# schematic_v2.net
KiCad netlist of a schematic drawn in EAGLE
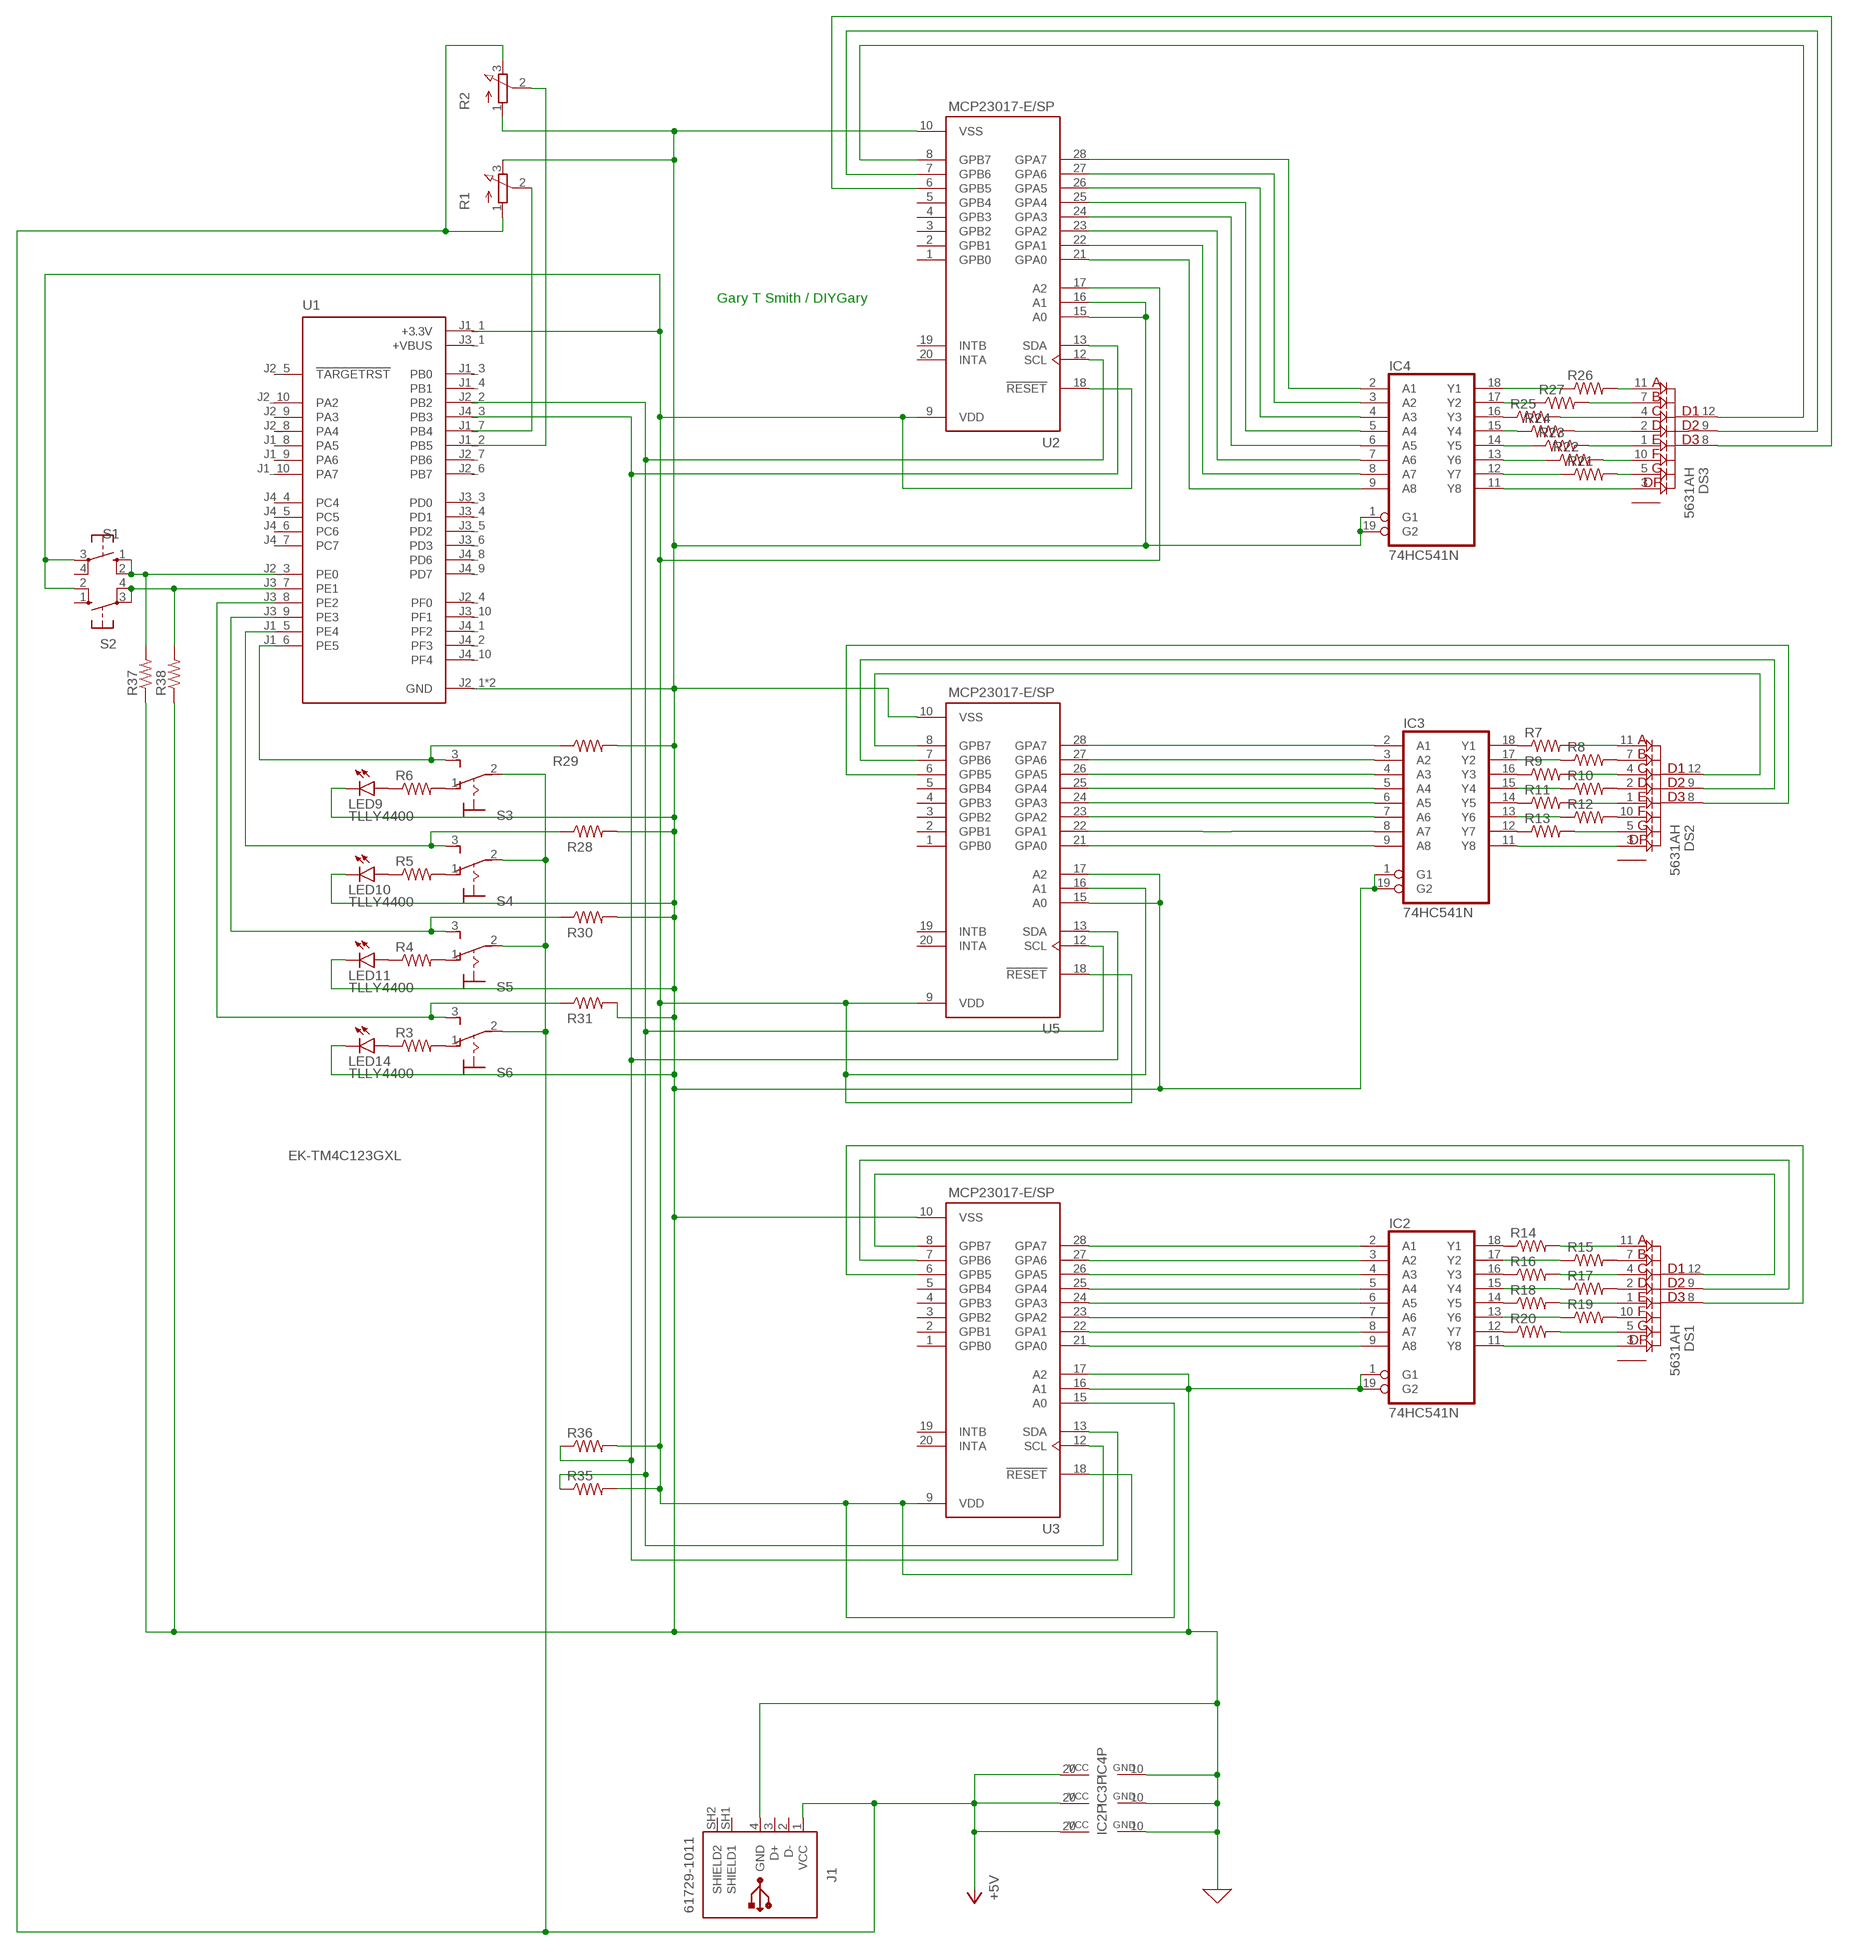
[diagram p0: schematic, sheet 1]

(export (version "E")
  (design (tool "Eeschema 10.0.6"))
  (components
    (comp (ref "DS1")
      (value "5631AH")
      (footprint "eagle-import:DIPS1524W50P254L3760H835Q12N")
      (fields
        (field (name "MANUFACTURER_PART_NUMBER") "BC56-12SRWA")
        (field (name "MOUSER_PART_NUMBER") "604-BC56-12SRWA")
      )
      (libsource (lib "eagle-import") (part "5631AH"))
    )
    (comp (ref "DS2")
      (value "5631AH")
      (footprint "eagle-import:DIPS1524W50P254L3760H835Q12N")
      (fields
        (field (name "MANUFACTURER_PART_NUMBER") "BC56-12SRWA")
        (field (name "MOUSER_PART_NUMBER") "604-BC56-12SRWA")
      )
      (libsource (lib "eagle-import") (part "5631AH"))
    )
    (comp (ref "DS3")
      (value "5631AH")
      (footprint "eagle-import:DIPS1524W50P254L3760H835Q12N")
      (fields
        (field (name "MANUFACTURER_PART_NUMBER") "BC56-12SRWA")
        (field (name "MOUSER_PART_NUMBER") "604-BC56-12SRWA")
      )
      (libsource (lib "eagle-import") (part "5631AH"))
    )
    (comp (ref "IC2")
      (value "74HC541N")
      (footprint "eagle-import:DIL20")
      (libsource (lib "eagle-import") (part "74541NHC"))
    )
    (comp (ref "IC3")
      (value "74HC541N")
      (footprint "eagle-import:DIL20")
      (libsource (lib "eagle-import") (part "74541NHC"))
    )
    (comp (ref "IC4")
      (value "74HC541N")
      (footprint "eagle-import:DIL20")
      (libsource (lib "eagle-import") (part "74541NHC"))
    )
    (comp (ref "J1")
      (value "61729-1011")
      (footprint "eagle-import:61729-1011BLF")
      (fields (field (name "MANUFACTURER") "Amphenol ICC (FCI)") (field (name "MPN") "61729-1011BLF"))
      (libsource (lib "eagle-import") (part "61729-1011"))
    )
    (comp (ref "LED9")
      (value "TLLY4400")
      (footprint "eagle-import:LED3MM")
      (fields (field (name "MF") "VISHAY SEMICONDUCTOR"))
      (libsource (lib "eagle-import") (part "TLLY4400"))
    )
    (comp (ref "LED10")
      (value "TLLY4400")
      (footprint "eagle-import:LED3MM")
      (fields (field (name "MF") "VISHAY SEMICONDUCTOR"))
      (libsource (lib "eagle-import") (part "TLLY4400"))
    )
    (comp (ref "LED11")
      (value "TLLY4400")
      (footprint "eagle-import:LED3MM")
      (fields (field (name "MF") "VISHAY SEMICONDUCTOR"))
      (libsource (lib "eagle-import") (part "TLLY4400"))
    )
    (comp (ref "LED14")
      (value "TLLY4400")
      (footprint "eagle-import:LED3MM")
      (fields (field (name "MF") "VISHAY SEMICONDUCTOR"))
      (libsource (lib "eagle-import") (part "TLLY4400"))
    )
    (comp (ref "R1")
      (value "3RP/1610N")
      (footprint "eagle-import:3RP_1610N")
      (libsource (lib "eagle-import") (part "3RP/1610N"))
    )
    (comp (ref "R2")
      (value "3RP/1610N")
      (footprint "eagle-import:3RP_1610N")
      (libsource (lib "eagle-import") (part "3RP/1610N"))
    )
    (comp (ref "R3")
      (value "R-US_0204/7")
      (footprint "eagle-import:0204_7")
      (libsource (lib "eagle-import") (part "R-US_0204/7"))
    )
    (comp (ref "R4")
      (value "R-US_0204/7")
      (footprint "eagle-import:0204_7")
      (libsource (lib "eagle-import") (part "R-US_0204/7"))
    )
    (comp (ref "R5")
      (value "R-US_0204/7")
      (footprint "eagle-import:0204_7")
      (libsource (lib "eagle-import") (part "R-US_0204/7"))
    )
    (comp (ref "R6")
      (value "R-US_0204/7")
      (footprint "eagle-import:0204_7")
      (libsource (lib "eagle-import") (part "R-US_0204/7"))
    )
    (comp (ref "R7")
      (value "R-US_0204/7")
      (footprint "eagle-import:0204_7")
      (libsource (lib "eagle-import") (part "R-US_0204/7"))
    )
    (comp (ref "R8")
      (value "R-US_0204/7")
      (footprint "eagle-import:0204_7")
      (libsource (lib "eagle-import") (part "R-US_0204/7"))
    )
    (comp (ref "R9")
      (value "R-US_0204/7")
      (footprint "eagle-import:0204_7")
      (libsource (lib "eagle-import") (part "R-US_0204/7"))
    )
    (comp (ref "R10")
      (value "R-US_0204/7")
      (footprint "eagle-import:0204_7")
      (libsource (lib "eagle-import") (part "R-US_0204/7"))
    )
    (comp (ref "R11")
      (value "R-US_0204/7")
      (footprint "eagle-import:0204_7")
      (libsource (lib "eagle-import") (part "R-US_0204/7"))
    )
    (comp (ref "R12")
      (value "R-US_0204/7")
      (footprint "eagle-import:0204_7")
      (libsource (lib "eagle-import") (part "R-US_0204/7"))
    )
    (comp (ref "R13")
      (value "R-US_0204/7")
      (footprint "eagle-import:0204_7")
      (libsource (lib "eagle-import") (part "R-US_0204/7"))
    )
    (comp (ref "R14")
      (value "R-US_0204/7")
      (footprint "eagle-import:0204_7")
      (libsource (lib "eagle-import") (part "R-US_0204/7"))
    )
    (comp (ref "R15")
      (value "R-US_0204/7")
      (footprint "eagle-import:0204_7")
      (libsource (lib "eagle-import") (part "R-US_0204/7"))
    )
    (comp (ref "R16")
      (value "R-US_0204/7")
      (footprint "eagle-import:0204_7")
      (libsource (lib "eagle-import") (part "R-US_0204/7"))
    )
    (comp (ref "R17")
      (value "R-US_0204/7")
      (footprint "eagle-import:0204_7")
      (libsource (lib "eagle-import") (part "R-US_0204/7"))
    )
    (comp (ref "R18")
      (value "R-US_0204/7")
      (footprint "eagle-import:0204_7")
      (libsource (lib "eagle-import") (part "R-US_0204/7"))
    )
    (comp (ref "R19")
      (value "R-US_0204/7")
      (footprint "eagle-import:0204_7")
      (libsource (lib "eagle-import") (part "R-US_0204/7"))
    )
    (comp (ref "R20")
      (value "R-US_0204/7")
      (footprint "eagle-import:0204_7")
      (libsource (lib "eagle-import") (part "R-US_0204/7"))
    )
    (comp (ref "R21")
      (value "R-US_0204/7")
      (footprint "eagle-import:0204_7")
      (libsource (lib "eagle-import") (part "R-US_0204/7"))
    )
    (comp (ref "R22")
      (value "R-US_0204/7")
      (footprint "eagle-import:0204_7")
      (libsource (lib "eagle-import") (part "R-US_0204/7"))
    )
    (comp (ref "R23")
      (value "R-US_0204/7")
      (footprint "eagle-import:0204_7")
      (libsource (lib "eagle-import") (part "R-US_0204/7"))
    )
    (comp (ref "R24")
      (value "R-US_0204/7")
      (footprint "eagle-import:0204_7")
      (libsource (lib "eagle-import") (part "R-US_0204/7"))
    )
    (comp (ref "R25")
      (value "R-US_0204/7")
      (footprint "eagle-import:0204_7")
      (libsource (lib "eagle-import") (part "R-US_0204/7"))
    )
    (comp (ref "R26")
      (value "R-US_0204/7")
      (footprint "eagle-import:0204_7")
      (libsource (lib "eagle-import") (part "R-US_0204/7"))
    )
    (comp (ref "R27")
      (value "R-US_0204/7")
      (footprint "eagle-import:0204_7")
      (libsource (lib "eagle-import") (part "R-US_0204/7"))
    )
    (comp (ref "R28")
      (value "R-US_0204/7")
      (footprint "eagle-import:0204_7")
      (libsource (lib "eagle-import") (part "R-US_0204/7"))
    )
    (comp (ref "R29")
      (value "R-US_0204/7")
      (footprint "eagle-import:0204_7")
      (libsource (lib "eagle-import") (part "R-US_0204/7"))
    )
    (comp (ref "R30")
      (value "R-US_0204/7")
      (footprint "eagle-import:0204_7")
      (libsource (lib "eagle-import") (part "R-US_0204/7"))
    )
    (comp (ref "R31")
      (value "R-US_0204/7")
      (footprint "eagle-import:0204_7")
      (libsource (lib "eagle-import") (part "R-US_0204/7"))
    )
    (comp (ref "R35")
      (value "R-US_0204/7")
      (footprint "eagle-import:0204_7")
      (libsource (lib "eagle-import") (part "R-US_0204/7"))
    )
    (comp (ref "R36")
      (value "R-US_0204/7")
      (footprint "eagle-import:0204_7")
      (libsource (lib "eagle-import") (part "R-US_0204/7"))
    )
    (comp (ref "R37")
      (value "R-US_0204/7")
      (footprint "eagle-import:0204_7")
      (libsource (lib "eagle-import") (part "R-US_0204/7"))
    )
    (comp (ref "R38")
      (value "R-US_0204/7")
      (footprint "eagle-import:0204_7")
      (libsource (lib "eagle-import") (part "R-US_0204/7"))
    )
    (comp (ref "S1")
      (value "10-XX")
      (footprint "eagle-import:B3F-10XX")
      (fields (field (name "MPN") "B3F-1000"))
      (libsource (lib "eagle-import") (part "10-XX"))
    )
    (comp (ref "S2")
      (value "10-XX")
      (footprint "eagle-import:B3F-10XX")
      (fields (field (name "MPN") "B3F-1000"))
      (libsource (lib "eagle-import") (part "10-XX"))
    )
    (comp (ref "S3")
      (value "320-916")
      (footprint "eagle-import:320-916")
      (libsource (lib "eagle-import") (part "320-916"))
    )
    (comp (ref "S4")
      (value "320-916")
      (footprint "eagle-import:320-916")
      (libsource (lib "eagle-import") (part "320-916"))
    )
    (comp (ref "S5")
      (value "320-916")
      (footprint "eagle-import:320-916")
      (libsource (lib "eagle-import") (part "320-916"))
    )
    (comp (ref "S6")
      (value "320-916")
      (footprint "eagle-import:320-916")
      (libsource (lib "eagle-import") (part "320-916"))
    )
    (comp (ref "U1")
      (value "EK-TM4C123GXL")
      (footprint "eagle-import:MODULE_EK-TM4C123GXL")
      (fields (field (name "MF") "Texas Instruments"))
      (libsource (lib "eagle-import") (part "EK-TM4C123GXL"))
    )
    (comp (ref "U2")
      (value "MCP23017-E/SP")
      (footprint "eagle-import:DIP787W45P254L3556H508Q28")
      (fields (field (name "MF") "Microchip Technology"))
      (libsource (lib "eagle-import") (part "MCP23017-E/SP"))
    )
    (comp (ref "U3")
      (value "MCP23017-E/SP")
      (footprint "eagle-import:DIP787W45P254L3556H508Q28")
      (fields (field (name "MF") "Microchip Technology"))
      (libsource (lib "eagle-import") (part "MCP23017-E/SP"))
    )
    (comp (ref "U5")
      (value "MCP23017-E/SP")
      (footprint "eagle-import:DIP787W45P254L3556H508Q28")
      (fields (field (name "MF") "Microchip Technology"))
      (libsource (lib "eagle-import") (part "MCP23017-E/SP"))
    )
  )
  (nets
    (net (code "1") (name "+5V") (class "Default")
      (node (ref "IC2") (pin "20") (pinfunction "VCC_20") (pintype "power_in"))
      (node (ref "IC3") (pin "20") (pinfunction "VCC_20") (pintype "power_in"))
      (node (ref "IC4") (pin "20") (pinfunction "VCC_20") (pintype "power_in"))
      (node (ref "J1") (pin "1") (pinfunction "VCC_1") (pintype "power_in"))
      (node (ref "R1") (pin "1") (pinfunction "A_1") (pintype "passive"))
      (node (ref "R2") (pin "3") (pinfunction "E_3") (pintype "passive"))
      (node (ref "S3") (pin "2") (pinfunction "P_2") (pintype "passive"))
      (node (ref "S4") (pin "2") (pinfunction "P_2") (pintype "passive"))
      (node (ref "S5") (pin "2") (pinfunction "P_2") (pintype "passive"))
      (node (ref "S6") (pin "2") (pinfunction "P_2") (pintype "passive"))
    )
    (net (code "2") (name "/+VBUS") (class "Default")
      (node (ref "U1") (pin "J3_1") (pinfunction "+VBUS_J3_1") (pintype "power_in"))
    )
    (net (code "3") (name "/SHIELD1") (class "Default")
      (node (ref "J1") (pin "SH1") (pinfunction "SHIELD1_SH1") (pintype "power_in"))
    )
    (net (code "4") (name "/SHIELD2") (class "Default")
      (node (ref "J1") (pin "SH2") (pinfunction "SHIELD2_SH2") (pintype "power_in"))
    )
    (net (code "5") (name "GND") (class "Default")
      (node (ref "IC2") (pin "1") (pinfunction "G1_1") (pintype "input"))
      (node (ref "IC2") (pin "10") (pinfunction "GND_10") (pintype "power_in"))
      (node (ref "IC2") (pin "19") (pinfunction "G2_19") (pintype "input"))
      (node (ref "IC3") (pin "1") (pinfunction "G1_1") (pintype "input"))
      (node (ref "IC3") (pin "10") (pinfunction "GND_10") (pintype "power_in"))
      (node (ref "IC3") (pin "19") (pinfunction "G2_19") (pintype "input"))
      (node (ref "IC4") (pin "1") (pinfunction "G1_1") (pintype "input"))
      (node (ref "IC4") (pin "10") (pinfunction "GND_10") (pintype "power_in"))
      (node (ref "IC4") (pin "19") (pinfunction "G2_19") (pintype "input"))
      (node (ref "J1") (pin "4") (pinfunction "GND_4") (pintype "power_in"))
      (node (ref "LED10") (pin "K") (pinfunction "C_K") (pintype "passive"))
      (node (ref "LED11") (pin "K") (pinfunction "C_K") (pintype "passive"))
      (node (ref "LED14") (pin "K") (pinfunction "C_K") (pintype "passive"))
      (node (ref "LED9") (pin "K") (pinfunction "C_K") (pintype "passive"))
      (node (ref "R1") (pin "3") (pinfunction "E_3") (pintype "passive"))
      (node (ref "R2") (pin "1") (pinfunction "A_1") (pintype "passive"))
      (node (ref "R28") (pin "2") (pinfunction "2_2") (pintype "passive"))
      (node (ref "R29") (pin "2") (pinfunction "2_2") (pintype "passive"))
      (node (ref "R30") (pin "2") (pinfunction "2_2") (pintype "passive"))
      (node (ref "R31") (pin "2") (pinfunction "2_2") (pintype "passive"))
      (node (ref "R37") (pin "1") (pinfunction "1_1") (pintype "passive"))
      (node (ref "R38") (pin "1") (pinfunction "1_1") (pintype "passive"))
      (node (ref "U1") (pin "J2_1") (pinfunction "GND_J2_1") (pintype "power_in"))
      (node (ref "U1") (pin "J3_2") (pinfunction "GND_J3_2") (pintype "power_in"))
      (node (ref "U2") (pin "10") (pinfunction "VSS_10") (pintype "power_in"))
      (node (ref "U2") (pin "15") (pinfunction "A0_15") (pintype "input"))
      (node (ref "U2") (pin "16") (pinfunction "A1_16") (pintype "input"))
      (node (ref "U3") (pin "10") (pinfunction "VSS_10") (pintype "power_in"))
      (node (ref "U3") (pin "16") (pinfunction "A1_16") (pintype "input"))
      (node (ref "U3") (pin "17") (pinfunction "A2_17") (pintype "input"))
      (node (ref "U5") (pin "10") (pinfunction "VSS_10") (pintype "power_in"))
      (node (ref "U5") (pin "15") (pinfunction "A0_15") (pintype "input"))
      (node (ref "U5") (pin "17") (pinfunction "A2_17") (pintype "input"))
    )
    (net (code "6") (name "Net-(DS1-A_A)") (class "Default")
      (node (ref "DS1") (pin "11") (pinfunction "A_A_11") (pintype "bidirectional"))
      (node (ref "R14") (pin "2") (pinfunction "2_2") (pintype "passive"))
    )
    (net (code "7") (name "Net-(DS1-A_B)") (class "Default")
      (node (ref "DS1") (pin "7") (pinfunction "A_B_7") (pintype "bidirectional"))
      (node (ref "R15") (pin "2") (pinfunction "2_2") (pintype "passive"))
    )
    (net (code "8") (name "Net-(DS1-A_C)") (class "Default")
      (node (ref "DS1") (pin "4") (pinfunction "A_C_4") (pintype "bidirectional"))
      (node (ref "R16") (pin "2") (pinfunction "2_2") (pintype "passive"))
    )
    (net (code "9") (name "Net-(DS1-A_D)") (class "Default")
      (node (ref "DS1") (pin "2") (pinfunction "A_D_2") (pintype "bidirectional"))
      (node (ref "R17") (pin "2") (pinfunction "2_2") (pintype "passive"))
    )
    (net (code "10") (name "Net-(DS1-A_DP)") (class "Default")
      (node (ref "DS1") (pin "3") (pinfunction "A_DP_3") (pintype "bidirectional"))
      (node (ref "IC2") (pin "11") (pinfunction "Y8_11") (pintype "tri_state"))
    )
    (net (code "11") (name "Net-(DS1-A_E)") (class "Default")
      (node (ref "DS1") (pin "1") (pinfunction "A_E_1") (pintype "bidirectional"))
      (node (ref "R18") (pin "2") (pinfunction "2_2") (pintype "passive"))
    )
    (net (code "12") (name "Net-(DS1-A_F)") (class "Default")
      (node (ref "DS1") (pin "10") (pinfunction "A_F_10") (pintype "bidirectional"))
      (node (ref "R19") (pin "2") (pinfunction "2_2") (pintype "passive"))
    )
    (net (code "13") (name "Net-(DS1-A_G)") (class "Default")
      (node (ref "DS1") (pin "5") (pinfunction "A_G_5") (pintype "bidirectional"))
      (node (ref "R20") (pin "2") (pinfunction "2_2") (pintype "passive"))
    )
    (net (code "14") (name "Net-(DS1-CC_D1)") (class "Default")
      (node (ref "DS1") (pin "12") (pinfunction "CC_D1_12") (pintype "bidirectional"))
      (node (ref "U3") (pin "8") (pinfunction "GPB7_8") (pintype "bidirectional"))
    )
    (net (code "15") (name "Net-(DS1-CC_D2)") (class "Default")
      (node (ref "DS1") (pin "9") (pinfunction "CC_D2_9") (pintype "bidirectional"))
      (node (ref "U3") (pin "7") (pinfunction "GPB6_7") (pintype "bidirectional"))
    )
    (net (code "16") (name "Net-(DS1-CC_D3)") (class "Default")
      (node (ref "DS1") (pin "8") (pinfunction "CC_D3_8") (pintype "bidirectional"))
      (node (ref "U3") (pin "6") (pinfunction "GPB5_6") (pintype "bidirectional"))
    )
    (net (code "17") (name "Net-(DS2-A_A)") (class "Default")
      (node (ref "DS2") (pin "11") (pinfunction "A_A_11") (pintype "bidirectional"))
      (node (ref "R7") (pin "2") (pinfunction "2_2") (pintype "passive"))
    )
    (net (code "18") (name "Net-(DS2-A_B)") (class "Default")
      (node (ref "DS2") (pin "7") (pinfunction "A_B_7") (pintype "bidirectional"))
      (node (ref "R8") (pin "2") (pinfunction "2_2") (pintype "passive"))
    )
    (net (code "19") (name "Net-(DS2-A_C)") (class "Default")
      (node (ref "DS2") (pin "4") (pinfunction "A_C_4") (pintype "bidirectional"))
      (node (ref "R9") (pin "2") (pinfunction "2_2") (pintype "passive"))
    )
    (net (code "20") (name "Net-(DS2-A_D)") (class "Default")
      (node (ref "DS2") (pin "2") (pinfunction "A_D_2") (pintype "bidirectional"))
      (node (ref "R10") (pin "2") (pinfunction "2_2") (pintype "passive"))
    )
    (net (code "21") (name "Net-(DS2-A_DP)") (class "Default")
      (node (ref "DS2") (pin "3") (pinfunction "A_DP_3") (pintype "bidirectional"))
      (node (ref "IC3") (pin "11") (pinfunction "Y8_11") (pintype "tri_state"))
    )
    (net (code "22") (name "Net-(DS2-A_E)") (class "Default")
      (node (ref "DS2") (pin "1") (pinfunction "A_E_1") (pintype "bidirectional"))
      (node (ref "R11") (pin "2") (pinfunction "2_2") (pintype "passive"))
    )
    (net (code "23") (name "Net-(DS2-A_F)") (class "Default")
      (node (ref "DS2") (pin "10") (pinfunction "A_F_10") (pintype "bidirectional"))
      (node (ref "R12") (pin "2") (pinfunction "2_2") (pintype "passive"))
    )
    (net (code "24") (name "Net-(DS2-A_G)") (class "Default")
      (node (ref "DS2") (pin "5") (pinfunction "A_G_5") (pintype "bidirectional"))
      (node (ref "R13") (pin "2") (pinfunction "2_2") (pintype "passive"))
    )
    (net (code "25") (name "Net-(DS2-CC_D1)") (class "Default")
      (node (ref "DS2") (pin "12") (pinfunction "CC_D1_12") (pintype "bidirectional"))
      (node (ref "U5") (pin "8") (pinfunction "GPB7_8") (pintype "bidirectional"))
    )
    (net (code "26") (name "Net-(DS2-CC_D2)") (class "Default")
      (node (ref "DS2") (pin "9") (pinfunction "CC_D2_9") (pintype "bidirectional"))
      (node (ref "U5") (pin "7") (pinfunction "GPB6_7") (pintype "bidirectional"))
    )
    (net (code "27") (name "Net-(DS2-CC_D3)") (class "Default")
      (node (ref "DS2") (pin "8") (pinfunction "CC_D3_8") (pintype "bidirectional"))
      (node (ref "U5") (pin "6") (pinfunction "GPB5_6") (pintype "bidirectional"))
    )
    (net (code "28") (name "Net-(DS3-A_A)") (class "Default")
      (node (ref "DS3") (pin "11") (pinfunction "A_A_11") (pintype "bidirectional"))
      (node (ref "R26") (pin "2") (pinfunction "2_2") (pintype "passive"))
    )
    (net (code "29") (name "Net-(DS3-A_B)") (class "Default")
      (node (ref "DS3") (pin "7") (pinfunction "A_B_7") (pintype "bidirectional"))
      (node (ref "R27") (pin "2") (pinfunction "2_2") (pintype "passive"))
    )
    (net (code "30") (name "Net-(DS3-A_C)") (class "Default")
      (node (ref "DS3") (pin "4") (pinfunction "A_C_4") (pintype "bidirectional"))
      (node (ref "R25") (pin "2") (pinfunction "2_2") (pintype "passive"))
    )
    (net (code "31") (name "Net-(DS3-A_D)") (class "Default")
      (node (ref "DS3") (pin "2") (pinfunction "A_D_2") (pintype "bidirectional"))
      (node (ref "R24") (pin "2") (pinfunction "2_2") (pintype "passive"))
    )
    (net (code "32") (name "Net-(DS3-A_DP)") (class "Default")
      (node (ref "DS3") (pin "3") (pinfunction "A_DP_3") (pintype "bidirectional"))
      (node (ref "IC4") (pin "11") (pinfunction "Y8_11") (pintype "tri_state"))
    )
    (net (code "33") (name "Net-(DS3-A_E)") (class "Default")
      (node (ref "DS3") (pin "1") (pinfunction "A_E_1") (pintype "bidirectional"))
      (node (ref "R23") (pin "2") (pinfunction "2_2") (pintype "passive"))
    )
    (net (code "34") (name "Net-(DS3-A_F)") (class "Default")
      (node (ref "DS3") (pin "10") (pinfunction "A_F_10") (pintype "bidirectional"))
      (node (ref "R22") (pin "2") (pinfunction "2_2") (pintype "passive"))
    )
    (net (code "35") (name "Net-(DS3-A_G)") (class "Default")
      (node (ref "DS3") (pin "5") (pinfunction "A_G_5") (pintype "bidirectional"))
      (node (ref "R21") (pin "2") (pinfunction "2_2") (pintype "passive"))
    )
    (net (code "36") (name "Net-(DS3-CC_D1)") (class "Default")
      (node (ref "DS3") (pin "12") (pinfunction "CC_D1_12") (pintype "bidirectional"))
      (node (ref "U2") (pin "8") (pinfunction "GPB7_8") (pintype "bidirectional"))
    )
    (net (code "37") (name "Net-(DS3-CC_D2)") (class "Default")
      (node (ref "DS3") (pin "9") (pinfunction "CC_D2_9") (pintype "bidirectional"))
      (node (ref "U2") (pin "7") (pinfunction "GPB6_7") (pintype "bidirectional"))
    )
    (net (code "38") (name "Net-(DS3-CC_D3)") (class "Default")
      (node (ref "DS3") (pin "8") (pinfunction "CC_D3_8") (pintype "bidirectional"))
      (node (ref "U2") (pin "6") (pinfunction "GPB5_6") (pintype "bidirectional"))
    )
    (net (code "39") (name "Net-(IC2A-A1)") (class "Default")
      (node (ref "IC2") (pin "2") (pinfunction "A1_2") (pintype "input"))
      (node (ref "U3") (pin "28") (pinfunction "GPA7_28") (pintype "bidirectional"))
    )
    (net (code "40") (name "Net-(IC2A-A2)") (class "Default")
      (node (ref "IC2") (pin "3") (pinfunction "A2_3") (pintype "input"))
      (node (ref "U3") (pin "27") (pinfunction "GPA6_27") (pintype "bidirectional"))
    )
    (net (code "41") (name "Net-(IC2A-A3)") (class "Default")
      (node (ref "IC2") (pin "4") (pinfunction "A3_4") (pintype "input"))
      (node (ref "U3") (pin "26") (pinfunction "GPA5_26") (pintype "bidirectional"))
    )
    (net (code "42") (name "Net-(IC2A-A4)") (class "Default")
      (node (ref "IC2") (pin "5") (pinfunction "A4_5") (pintype "input"))
      (node (ref "U3") (pin "25") (pinfunction "GPA4_25") (pintype "bidirectional"))
    )
    (net (code "43") (name "Net-(IC2A-A5)") (class "Default")
      (node (ref "IC2") (pin "6") (pinfunction "A5_6") (pintype "input"))
      (node (ref "U3") (pin "24") (pinfunction "GPA3_24") (pintype "bidirectional"))
    )
    (net (code "44") (name "Net-(IC2A-A6)") (class "Default")
      (node (ref "IC2") (pin "7") (pinfunction "A6_7") (pintype "input"))
      (node (ref "U3") (pin "23") (pinfunction "GPA2_23") (pintype "bidirectional"))
    )
    (net (code "45") (name "Net-(IC2A-A7)") (class "Default")
      (node (ref "IC2") (pin "8") (pinfunction "A7_8") (pintype "input"))
      (node (ref "U3") (pin "22") (pinfunction "GPA1_22") (pintype "bidirectional"))
    )
    (net (code "46") (name "Net-(IC2A-A8)") (class "Default")
      (node (ref "IC2") (pin "9") (pinfunction "A8_9") (pintype "input"))
      (node (ref "U3") (pin "21") (pinfunction "GPA0_21") (pintype "bidirectional"))
    )
    (net (code "47") (name "Net-(IC2A-Y1)") (class "Default")
      (node (ref "IC2") (pin "18") (pinfunction "Y1_18") (pintype "tri_state"))
      (node (ref "R14") (pin "1") (pinfunction "1_1") (pintype "passive"))
    )
    (net (code "48") (name "Net-(IC2A-Y2)") (class "Default")
      (node (ref "IC2") (pin "17") (pinfunction "Y2_17") (pintype "tri_state"))
      (node (ref "R15") (pin "1") (pinfunction "1_1") (pintype "passive"))
    )
    (net (code "49") (name "Net-(IC2A-Y3)") (class "Default")
      (node (ref "IC2") (pin "16") (pinfunction "Y3_16") (pintype "tri_state"))
      (node (ref "R16") (pin "1") (pinfunction "1_1") (pintype "passive"))
    )
    (net (code "50") (name "Net-(IC2A-Y4)") (class "Default")
      (node (ref "IC2") (pin "15") (pinfunction "Y4_15") (pintype "tri_state"))
      (node (ref "R17") (pin "1") (pinfunction "1_1") (pintype "passive"))
    )
    (net (code "51") (name "Net-(IC2A-Y5)") (class "Default")
      (node (ref "IC2") (pin "14") (pinfunction "Y5_14") (pintype "tri_state"))
      (node (ref "R18") (pin "1") (pinfunction "1_1") (pintype "passive"))
    )
    (net (code "52") (name "Net-(IC2A-Y6)") (class "Default")
      (node (ref "IC2") (pin "13") (pinfunction "Y6_13") (pintype "tri_state"))
      (node (ref "R19") (pin "1") (pinfunction "1_1") (pintype "passive"))
    )
    (net (code "53") (name "Net-(IC2A-Y7)") (class "Default")
      (node (ref "IC2") (pin "12") (pinfunction "Y7_12") (pintype "tri_state"))
      (node (ref "R20") (pin "1") (pinfunction "1_1") (pintype "passive"))
    )
    (net (code "54") (name "Net-(IC3A-A1)") (class "Default")
      (node (ref "IC3") (pin "2") (pinfunction "A1_2") (pintype "input"))
      (node (ref "U5") (pin "28") (pinfunction "GPA7_28") (pintype "bidirectional"))
    )
    (net (code "55") (name "Net-(IC3A-A2)") (class "Default")
      (node (ref "IC3") (pin "3") (pinfunction "A2_3") (pintype "input"))
      (node (ref "U5") (pin "27") (pinfunction "GPA6_27") (pintype "bidirectional"))
    )
    (net (code "56") (name "Net-(IC3A-A3)") (class "Default")
      (node (ref "IC3") (pin "4") (pinfunction "A3_4") (pintype "input"))
      (node (ref "U5") (pin "26") (pinfunction "GPA5_26") (pintype "bidirectional"))
    )
    (net (code "57") (name "Net-(IC3A-A4)") (class "Default")
      (node (ref "IC3") (pin "5") (pinfunction "A4_5") (pintype "input"))
      (node (ref "U5") (pin "25") (pinfunction "GPA4_25") (pintype "bidirectional"))
    )
    (net (code "58") (name "Net-(IC3A-A5)") (class "Default")
      (node (ref "IC3") (pin "6") (pinfunction "A5_6") (pintype "input"))
      (node (ref "U5") (pin "24") (pinfunction "GPA3_24") (pintype "bidirectional"))
    )
    (net (code "59") (name "Net-(IC3A-A6)") (class "Default")
      (node (ref "IC3") (pin "7") (pinfunction "A6_7") (pintype "input"))
      (node (ref "U5") (pin "23") (pinfunction "GPA2_23") (pintype "bidirectional"))
    )
    (net (code "60") (name "Net-(IC3A-A7)") (class "Default")
      (node (ref "IC3") (pin "8") (pinfunction "A7_8") (pintype "input"))
      (node (ref "U5") (pin "22") (pinfunction "GPA1_22") (pintype "bidirectional"))
    )
    (net (code "61") (name "Net-(IC3A-A8)") (class "Default")
      (node (ref "IC3") (pin "9") (pinfunction "A8_9") (pintype "input"))
      (node (ref "U5") (pin "21") (pinfunction "GPA0_21") (pintype "bidirectional"))
    )
    (net (code "62") (name "Net-(IC3A-Y1)") (class "Default")
      (node (ref "IC3") (pin "18") (pinfunction "Y1_18") (pintype "tri_state"))
      (node (ref "R7") (pin "1") (pinfunction "1_1") (pintype "passive"))
    )
    (net (code "63") (name "Net-(IC3A-Y2)") (class "Default")
      (node (ref "IC3") (pin "17") (pinfunction "Y2_17") (pintype "tri_state"))
      (node (ref "R8") (pin "1") (pinfunction "1_1") (pintype "passive"))
    )
    (net (code "64") (name "Net-(IC3A-Y3)") (class "Default")
      (node (ref "IC3") (pin "16") (pinfunction "Y3_16") (pintype "tri_state"))
      (node (ref "R9") (pin "1") (pinfunction "1_1") (pintype "passive"))
    )
    (net (code "65") (name "Net-(IC3A-Y4)") (class "Default")
      (node (ref "IC3") (pin "15") (pinfunction "Y4_15") (pintype "tri_state"))
      (node (ref "R10") (pin "1") (pinfunction "1_1") (pintype "passive"))
    )
    (net (code "66") (name "Net-(IC3A-Y5)") (class "Default")
      (node (ref "IC3") (pin "14") (pinfunction "Y5_14") (pintype "tri_state"))
      (node (ref "R11") (pin "1") (pinfunction "1_1") (pintype "passive"))
    )
    (net (code "67") (name "Net-(IC3A-Y6)") (class "Default")
      (node (ref "IC3") (pin "13") (pinfunction "Y6_13") (pintype "tri_state"))
      (node (ref "R12") (pin "1") (pinfunction "1_1") (pintype "passive"))
    )
    (net (code "68") (name "Net-(IC3A-Y7)") (class "Default")
      (node (ref "IC3") (pin "12") (pinfunction "Y7_12") (pintype "tri_state"))
      (node (ref "R13") (pin "1") (pinfunction "1_1") (pintype "passive"))
    )
    (net (code "69") (name "Net-(IC4A-A1)") (class "Default")
      (node (ref "IC4") (pin "2") (pinfunction "A1_2") (pintype "input"))
      (node (ref "U2") (pin "28") (pinfunction "GPA7_28") (pintype "bidirectional"))
    )
    (net (code "70") (name "Net-(IC4A-A2)") (class "Default")
      (node (ref "IC4") (pin "3") (pinfunction "A2_3") (pintype "input"))
      (node (ref "U2") (pin "27") (pinfunction "GPA6_27") (pintype "bidirectional"))
    )
    (net (code "71") (name "Net-(IC4A-A3)") (class "Default")
      (node (ref "IC4") (pin "4") (pinfunction "A3_4") (pintype "input"))
      (node (ref "U2") (pin "26") (pinfunction "GPA5_26") (pintype "bidirectional"))
    )
    (net (code "72") (name "Net-(IC4A-A4)") (class "Default")
      (node (ref "IC4") (pin "5") (pinfunction "A4_5") (pintype "input"))
      (node (ref "U2") (pin "25") (pinfunction "GPA4_25") (pintype "bidirectional"))
    )
    (net (code "73") (name "Net-(IC4A-A5)") (class "Default")
      (node (ref "IC4") (pin "6") (pinfunction "A5_6") (pintype "input"))
      (node (ref "U2") (pin "24") (pinfunction "GPA3_24") (pintype "bidirectional"))
    )
    (net (code "74") (name "Net-(IC4A-A6)") (class "Default")
      (node (ref "IC4") (pin "7") (pinfunction "A6_7") (pintype "input"))
      (node (ref "U2") (pin "23") (pinfunction "GPA2_23") (pintype "bidirectional"))
    )
    (net (code "75") (name "Net-(IC4A-A7)") (class "Default")
      (node (ref "IC4") (pin "8") (pinfunction "A7_8") (pintype "input"))
      (node (ref "U2") (pin "22") (pinfunction "GPA1_22") (pintype "bidirectional"))
    )
    (net (code "76") (name "Net-(IC4A-A8)") (class "Default")
      (node (ref "IC4") (pin "9") (pinfunction "A8_9") (pintype "input"))
      (node (ref "U2") (pin "21") (pinfunction "GPA0_21") (pintype "bidirectional"))
    )
    (net (code "77") (name "Net-(IC4A-Y1)") (class "Default")
      (node (ref "IC4") (pin "18") (pinfunction "Y1_18") (pintype "tri_state"))
      (node (ref "R26") (pin "1") (pinfunction "1_1") (pintype "passive"))
    )
    (net (code "78") (name "Net-(IC4A-Y2)") (class "Default")
      (node (ref "IC4") (pin "17") (pinfunction "Y2_17") (pintype "tri_state"))
      (node (ref "R27") (pin "1") (pinfunction "1_1") (pintype "passive"))
    )
    (net (code "79") (name "Net-(IC4A-Y3)") (class "Default")
      (node (ref "IC4") (pin "16") (pinfunction "Y3_16") (pintype "tri_state"))
      (node (ref "R25") (pin "1") (pinfunction "1_1") (pintype "passive"))
    )
    (net (code "80") (name "Net-(IC4A-Y4)") (class "Default")
      (node (ref "IC4") (pin "15") (pinfunction "Y4_15") (pintype "tri_state"))
      (node (ref "R24") (pin "1") (pinfunction "1_1") (pintype "passive"))
    )
    (net (code "81") (name "Net-(IC4A-Y5)") (class "Default")
      (node (ref "IC4") (pin "14") (pinfunction "Y5_14") (pintype "tri_state"))
      (node (ref "R23") (pin "1") (pinfunction "1_1") (pintype "passive"))
    )
    (net (code "82") (name "Net-(IC4A-Y6)") (class "Default")
      (node (ref "IC4") (pin "13") (pinfunction "Y6_13") (pintype "tri_state"))
      (node (ref "R22") (pin "1") (pinfunction "1_1") (pintype "passive"))
    )
    (net (code "83") (name "Net-(IC4A-Y7)") (class "Default")
      (node (ref "IC4") (pin "12") (pinfunction "Y7_12") (pintype "tri_state"))
      (node (ref "R21") (pin "1") (pinfunction "1_1") (pintype "passive"))
    )
    (net (code "84") (name "Net-(LED9-PadA)") (class "Default")
      (node (ref "LED9") (pin "A") (pinfunction "A_A") (pintype "passive"))
      (node (ref "R6") (pin "1") (pinfunction "1_1") (pintype "passive"))
    )
    (net (code "85") (name "Net-(LED10-PadA)") (class "Default")
      (node (ref "LED10") (pin "A") (pinfunction "A_A") (pintype "passive"))
      (node (ref "R5") (pin "1") (pinfunction "1_1") (pintype "passive"))
    )
    (net (code "86") (name "Net-(LED11-PadA)") (class "Default")
      (node (ref "LED11") (pin "A") (pinfunction "A_A") (pintype "passive"))
      (node (ref "R4") (pin "1") (pinfunction "1_1") (pintype "passive"))
    )
    (net (code "87") (name "Net-(LED14-PadA)") (class "Default")
      (node (ref "LED14") (pin "A") (pinfunction "A_A") (pintype "passive"))
      (node (ref "R3") (pin "1") (pinfunction "1_1") (pintype "passive"))
    )
    (net (code "88") (name "Net-(R1-S)") (class "Default")
      (node (ref "R1") (pin "2") (pinfunction "S_2") (pintype "passive"))
      (node (ref "U1") (pin "J1_7") (pinfunction "PB4_J1_7") (pintype "bidirectional"))
    )
    (net (code "89") (name "Net-(R2-S)") (class "Default")
      (node (ref "R2") (pin "2") (pinfunction "S_2") (pintype "passive"))
      (node (ref "U1") (pin "J1_2") (pinfunction "PB5_J1_2") (pintype "bidirectional"))
    )
    (net (code "90") (name "Net-(S1-P)") (class "Default")
      (node (ref "R35") (pin "2") (pinfunction "2_2") (pintype "passive"))
      (node (ref "R36") (pin "2") (pinfunction "2_2") (pintype "passive"))
      (node (ref "S1") (pin "3") (pinfunction "P_3") (pintype "passive"))
      (node (ref "S2") (pin "2") (pinfunction "S1_2") (pintype "passive"))
      (node (ref "U1") (pin "J1_1") (pinfunction "+3.3V_J1_1") (pintype "power_in"))
      (node (ref "U2") (pin "17") (pinfunction "A2_17") (pintype "input"))
      (node (ref "U2") (pin "18") (pinfunction "~{RESET}_18") (pintype "input"))
      (node (ref "U2") (pin "9") (pinfunction "VDD_9") (pintype "power_in"))
      (node (ref "U3") (pin "15") (pinfunction "A0_15") (pintype "input"))
      (node (ref "U3") (pin "18") (pinfunction "~{RESET}_18") (pintype "input"))
      (node (ref "U3") (pin "9") (pinfunction "VDD_9") (pintype "power_in"))
      (node (ref "U5") (pin "16") (pinfunction "A1_16") (pintype "input"))
      (node (ref "U5") (pin "18") (pinfunction "~{RESET}_18") (pintype "input"))
      (node (ref "U5") (pin "9") (pinfunction "VDD_9") (pintype "power_in"))
    )
    (net (code "91") (name "Net-(S1-S)") (class "Default")
      (node (ref "R37") (pin "2") (pinfunction "2_2") (pintype "passive"))
      (node (ref "S1") (pin "1") (pinfunction "S_1") (pintype "passive"))
      (node (ref "S1") (pin "2") (pinfunction "S1_2") (pintype "passive"))
      (node (ref "U1") (pin "J2_3") (pinfunction "PE0_J2_3") (pintype "bidirectional"))
    )
    (net (code "92") (name "Net-(S2-P)") (class "Default")
      (node (ref "R38") (pin "2") (pinfunction "2_2") (pintype "passive"))
      (node (ref "S2") (pin "3") (pinfunction "P_3") (pintype "passive"))
      (node (ref "S2") (pin "4") (pinfunction "P1_4") (pintype "passive"))
      (node (ref "U1") (pin "J3_7") (pinfunction "PE1_J3_7") (pintype "bidirectional"))
    )
    (net (code "93") (name "Net-(S3-O)") (class "Default")
      (node (ref "R6") (pin "2") (pinfunction "2_2") (pintype "passive"))
      (node (ref "S3") (pin "1") (pinfunction "O_1") (pintype "passive"))
    )
    (net (code "94") (name "Net-(S3-S)") (class "Default")
      (node (ref "R29") (pin "1") (pinfunction "1_1") (pintype "passive"))
      (node (ref "S3") (pin "3") (pinfunction "S_3") (pintype "passive"))
      (node (ref "U1") (pin "J1_6") (pinfunction "PE5_J1_6") (pintype "bidirectional"))
    )
    (net (code "95") (name "Net-(S4-O)") (class "Default")
      (node (ref "R5") (pin "2") (pinfunction "2_2") (pintype "passive"))
      (node (ref "S4") (pin "1") (pinfunction "O_1") (pintype "passive"))
    )
    (net (code "96") (name "Net-(S4-S)") (class "Default")
      (node (ref "R28") (pin "1") (pinfunction "1_1") (pintype "passive"))
      (node (ref "S4") (pin "3") (pinfunction "S_3") (pintype "passive"))
      (node (ref "U1") (pin "J1_5") (pinfunction "PE4_J1_5") (pintype "bidirectional"))
    )
    (net (code "97") (name "Net-(S5-O)") (class "Default")
      (node (ref "R4") (pin "2") (pinfunction "2_2") (pintype "passive"))
      (node (ref "S5") (pin "1") (pinfunction "O_1") (pintype "passive"))
    )
    (net (code "98") (name "Net-(S5-S)") (class "Default")
      (node (ref "R30") (pin "1") (pinfunction "1_1") (pintype "passive"))
      (node (ref "S5") (pin "3") (pinfunction "S_3") (pintype "passive"))
      (node (ref "U1") (pin "J3_9") (pinfunction "PE3_J3_9") (pintype "bidirectional"))
    )
    (net (code "99") (name "Net-(S6-O)") (class "Default")
      (node (ref "R3") (pin "2") (pinfunction "2_2") (pintype "passive"))
      (node (ref "S6") (pin "1") (pinfunction "O_1") (pintype "passive"))
    )
    (net (code "100") (name "Net-(S6-S)") (class "Default")
      (node (ref "R31") (pin "1") (pinfunction "1_1") (pintype "passive"))
      (node (ref "S6") (pin "3") (pinfunction "S_3") (pintype "passive"))
      (node (ref "U1") (pin "J3_8") (pinfunction "PE2_J3_8") (pintype "bidirectional"))
    )
    (net (code "101") (name "Net-(U1-PB2)") (class "Default")
      (node (ref "R35") (pin "1") (pinfunction "1_1") (pintype "passive"))
      (node (ref "U1") (pin "J2_2") (pinfunction "PB2_J2_2") (pintype "bidirectional"))
      (node (ref "U2") (pin "12") (pinfunction "SCL_12") (pintype "input"))
      (node (ref "U3") (pin "12") (pinfunction "SCL_12") (pintype "input"))
      (node (ref "U5") (pin "12") (pinfunction "SCL_12") (pintype "input"))
    )
    (net (code "102") (name "Net-(U1-PB3)") (class "Default")
      (node (ref "R36") (pin "1") (pinfunction "1_1") (pintype "passive"))
      (node (ref "U1") (pin "J4_3") (pinfunction "PB3_J4_3") (pintype "bidirectional"))
      (node (ref "U2") (pin "13") (pinfunction "SDA_13") (pintype "bidirectional"))
      (node (ref "U3") (pin "13") (pinfunction "SDA_13") (pintype "bidirectional"))
      (node (ref "U5") (pin "13") (pinfunction "SDA_13") (pintype "bidirectional"))
    )
    (net (code "103") (name "unconnected-(DS1-NC-Pad6)") (class "Default")
      (node (ref "DS1") (pin "6") (pinfunction "NC_6") (pintype "no_connect"))
    )
    (net (code "104") (name "unconnected-(DS2-NC-Pad6)") (class "Default")
      (node (ref "DS2") (pin "6") (pinfunction "NC_6") (pintype "no_connect"))
    )
    (net (code "105") (name "unconnected-(DS3-NC-Pad6)") (class "Default")
      (node (ref "DS3") (pin "6") (pinfunction "NC_6") (pintype "no_connect"))
    )
    (net (code "106") (name "unconnected-(J1-D+-Pad3)") (class "Default")
      (node (ref "J1") (pin "3") (pinfunction "D+_3") (pintype "bidirectional"))
    )
    (net (code "107") (name "unconnected-(J1-D--Pad2)") (class "Default")
      (node (ref "J1") (pin "2") (pinfunction "D-_2") (pintype "bidirectional"))
    )
    (net (code "108") (name "unconnected-(S1-P1-Pad4)") (class "Default")
      (node (ref "S1") (pin "4") (pinfunction "P1_4") (pintype "passive"))
    )
    (net (code "109") (name "unconnected-(S2-S-Pad1)") (class "Default")
      (node (ref "S2") (pin "1") (pinfunction "S_1") (pintype "passive"))
    )
    (net (code "110") (name "unconnected-(U1-PA2-PadJ2_10)") (class "Default")
      (node (ref "U1") (pin "J2_10") (pinfunction "PA2_J2_10") (pintype "bidirectional"))
    )
    (net (code "111") (name "unconnected-(U1-PA3-PadJ2_9)") (class "Default")
      (node (ref "U1") (pin "J2_9") (pinfunction "PA3_J2_9") (pintype "bidirectional"))
    )
    (net (code "112") (name "unconnected-(U1-PA4-PadJ2_8)") (class "Default")
      (node (ref "U1") (pin "J2_8") (pinfunction "PA4_J2_8") (pintype "bidirectional"))
    )
    (net (code "113") (name "unconnected-(U1-PA5-PadJ1_8)") (class "Default")
      (node (ref "U1") (pin "J1_8") (pinfunction "PA5_J1_8") (pintype "bidirectional"))
    )
    (net (code "114") (name "unconnected-(U1-PA6-PadJ1_9)") (class "Default")
      (node (ref "U1") (pin "J1_9") (pinfunction "PA6_J1_9") (pintype "bidirectional"))
    )
    (net (code "115") (name "unconnected-(U1-PA7-PadJ1_10)") (class "Default")
      (node (ref "U1") (pin "J1_10") (pinfunction "PA7_J1_10") (pintype "bidirectional"))
    )
    (net (code "116") (name "unconnected-(U1-PB0-PadJ1_3)") (class "Default")
      (node (ref "U1") (pin "J1_3") (pinfunction "PB0_J1_3") (pintype "bidirectional"))
    )
    (net (code "117") (name "unconnected-(U1-PB1-PadJ1_4)") (class "Default")
      (node (ref "U1") (pin "J1_4") (pinfunction "PB1_J1_4") (pintype "bidirectional"))
    )
    (net (code "118") (name "unconnected-(U1-PB6-PadJ2_7)") (class "Default")
      (node (ref "U1") (pin "J2_7") (pinfunction "PB6_J2_7") (pintype "bidirectional"))
    )
    (net (code "119") (name "unconnected-(U1-PB7-PadJ2_6)") (class "Default")
      (node (ref "U1") (pin "J2_6") (pinfunction "PB7_J2_6") (pintype "bidirectional"))
    )
    (net (code "120") (name "unconnected-(U1-PC4-PadJ4_4)") (class "Default")
      (node (ref "U1") (pin "J4_4") (pinfunction "PC4_J4_4") (pintype "bidirectional"))
    )
    (net (code "121") (name "unconnected-(U1-PC5-PadJ4_5)") (class "Default")
      (node (ref "U1") (pin "J4_5") (pinfunction "PC5_J4_5") (pintype "bidirectional"))
    )
    (net (code "122") (name "unconnected-(U1-PC6-PadJ4_6)") (class "Default")
      (node (ref "U1") (pin "J4_6") (pinfunction "PC6_J4_6") (pintype "bidirectional"))
    )
    (net (code "123") (name "unconnected-(U1-PC7-PadJ4_7)") (class "Default")
      (node (ref "U1") (pin "J4_7") (pinfunction "PC7_J4_7") (pintype "bidirectional"))
    )
    (net (code "124") (name "unconnected-(U1-PD0-PadJ3_3)") (class "Default")
      (node (ref "U1") (pin "J3_3") (pinfunction "PD0_J3_3") (pintype "bidirectional"))
    )
    (net (code "125") (name "unconnected-(U1-PD1-PadJ3_4)") (class "Default")
      (node (ref "U1") (pin "J3_4") (pinfunction "PD1_J3_4") (pintype "bidirectional"))
    )
    (net (code "126") (name "unconnected-(U1-PD2-PadJ3_5)") (class "Default")
      (node (ref "U1") (pin "J3_5") (pinfunction "PD2_J3_5") (pintype "bidirectional"))
    )
    (net (code "127") (name "unconnected-(U1-PD3-PadJ3_6)") (class "Default")
      (node (ref "U1") (pin "J3_6") (pinfunction "PD3_J3_6") (pintype "bidirectional"))
    )
    (net (code "128") (name "unconnected-(U1-PD6-PadJ4_8)") (class "Default")
      (node (ref "U1") (pin "J4_8") (pinfunction "PD6_J4_8") (pintype "bidirectional"))
    )
    (net (code "129") (name "unconnected-(U1-PD7-PadJ4_9)") (class "Default")
      (node (ref "U1") (pin "J4_9") (pinfunction "PD7_J4_9") (pintype "bidirectional"))
    )
    (net (code "130") (name "unconnected-(U1-PF0-PadJ2_4)") (class "Default")
      (node (ref "U1") (pin "J2_4") (pinfunction "PF0_J2_4") (pintype "bidirectional"))
    )
    (net (code "131") (name "unconnected-(U1-PF1-PadJ3_10)") (class "Default")
      (node (ref "U1") (pin "J3_10") (pinfunction "PF1_J3_10") (pintype "bidirectional"))
    )
    (net (code "132") (name "unconnected-(U1-PF2-PadJ4_1)") (class "Default")
      (node (ref "U1") (pin "J4_1") (pinfunction "PF2_J4_1") (pintype "bidirectional"))
    )
    (net (code "133") (name "unconnected-(U1-PF3-PadJ4_2)") (class "Default")
      (node (ref "U1") (pin "J4_2") (pinfunction "PF3_J4_2") (pintype "bidirectional"))
    )
    (net (code "134") (name "unconnected-(U1-PF4-PadJ4_10)") (class "Default")
      (node (ref "U1") (pin "J4_10") (pinfunction "PF4_J4_10") (pintype "bidirectional"))
    )
    (net (code "135") (name "unconnected-(U1-~{TARGETRST}-PadJ2_5)") (class "Default")
      (node (ref "U1") (pin "J2_5") (pinfunction "~{TARGETRST}_J2_5") (pintype "input"))
    )
    (net (code "136") (name "unconnected-(U2-GPB0-Pad1)") (class "Default")
      (node (ref "U2") (pin "1") (pinfunction "GPB0_1") (pintype "bidirectional"))
    )
    (net (code "137") (name "unconnected-(U2-GPB1-Pad2)") (class "Default")
      (node (ref "U2") (pin "2") (pinfunction "GPB1_2") (pintype "bidirectional"))
    )
    (net (code "138") (name "unconnected-(U2-GPB2-Pad3)") (class "Default")
      (node (ref "U2") (pin "3") (pinfunction "GPB2_3") (pintype "bidirectional"))
    )
    (net (code "139") (name "unconnected-(U2-GPB3-Pad4)") (class "Default")
      (node (ref "U2") (pin "4") (pinfunction "GPB3_4") (pintype "bidirectional"))
    )
    (net (code "140") (name "unconnected-(U2-GPB4-Pad5)") (class "Default")
      (node (ref "U2") (pin "5") (pinfunction "GPB4_5") (pintype "bidirectional"))
    )
    (net (code "141") (name "unconnected-(U2-INTA-Pad20)") (class "Default")
      (node (ref "U2") (pin "20") (pinfunction "INTA_20") (pintype "output"))
    )
    (net (code "142") (name "unconnected-(U2-INTB-Pad19)") (class "Default")
      (node (ref "U2") (pin "19") (pinfunction "INTB_19") (pintype "output"))
    )
    (net (code "143") (name "unconnected-(U3-GPB0-Pad1)") (class "Default")
      (node (ref "U3") (pin "1") (pinfunction "GPB0_1") (pintype "bidirectional"))
    )
    (net (code "144") (name "unconnected-(U3-GPB1-Pad2)") (class "Default")
      (node (ref "U3") (pin "2") (pinfunction "GPB1_2") (pintype "bidirectional"))
    )
    (net (code "145") (name "unconnected-(U3-GPB2-Pad3)") (class "Default")
      (node (ref "U3") (pin "3") (pinfunction "GPB2_3") (pintype "bidirectional"))
    )
    (net (code "146") (name "unconnected-(U3-GPB3-Pad4)") (class "Default")
      (node (ref "U3") (pin "4") (pinfunction "GPB3_4") (pintype "bidirectional"))
    )
    (net (code "147") (name "unconnected-(U3-GPB4-Pad5)") (class "Default")
      (node (ref "U3") (pin "5") (pinfunction "GPB4_5") (pintype "bidirectional"))
    )
    (net (code "148") (name "unconnected-(U3-INTA-Pad20)") (class "Default")
      (node (ref "U3") (pin "20") (pinfunction "INTA_20") (pintype "output"))
    )
    (net (code "149") (name "unconnected-(U3-INTB-Pad19)") (class "Default")
      (node (ref "U3") (pin "19") (pinfunction "INTB_19") (pintype "output"))
    )
    (net (code "150") (name "unconnected-(U5-GPB0-Pad1)") (class "Default")
      (node (ref "U5") (pin "1") (pinfunction "GPB0_1") (pintype "bidirectional"))
    )
    (net (code "151") (name "unconnected-(U5-GPB1-Pad2)") (class "Default")
      (node (ref "U5") (pin "2") (pinfunction "GPB1_2") (pintype "bidirectional"))
    )
    (net (code "152") (name "unconnected-(U5-GPB2-Pad3)") (class "Default")
      (node (ref "U5") (pin "3") (pinfunction "GPB2_3") (pintype "bidirectional"))
    )
    (net (code "153") (name "unconnected-(U5-GPB3-Pad4)") (class "Default")
      (node (ref "U5") (pin "4") (pinfunction "GPB3_4") (pintype "bidirectional"))
    )
    (net (code "154") (name "unconnected-(U5-GPB4-Pad5)") (class "Default")
      (node (ref "U5") (pin "5") (pinfunction "GPB4_5") (pintype "bidirectional"))
    )
    (net (code "155") (name "unconnected-(U5-INTA-Pad20)") (class "Default")
      (node (ref "U5") (pin "20") (pinfunction "INTA_20") (pintype "output"))
    )
    (net (code "156") (name "unconnected-(U5-INTB-Pad19)") (class "Default")
      (node (ref "U5") (pin "19") (pinfunction "INTB_19") (pintype "output"))
    )
  )
)
